# Escorna_CPU_1_01.net
KiCad netlist of a schematic drawn in EAGLE
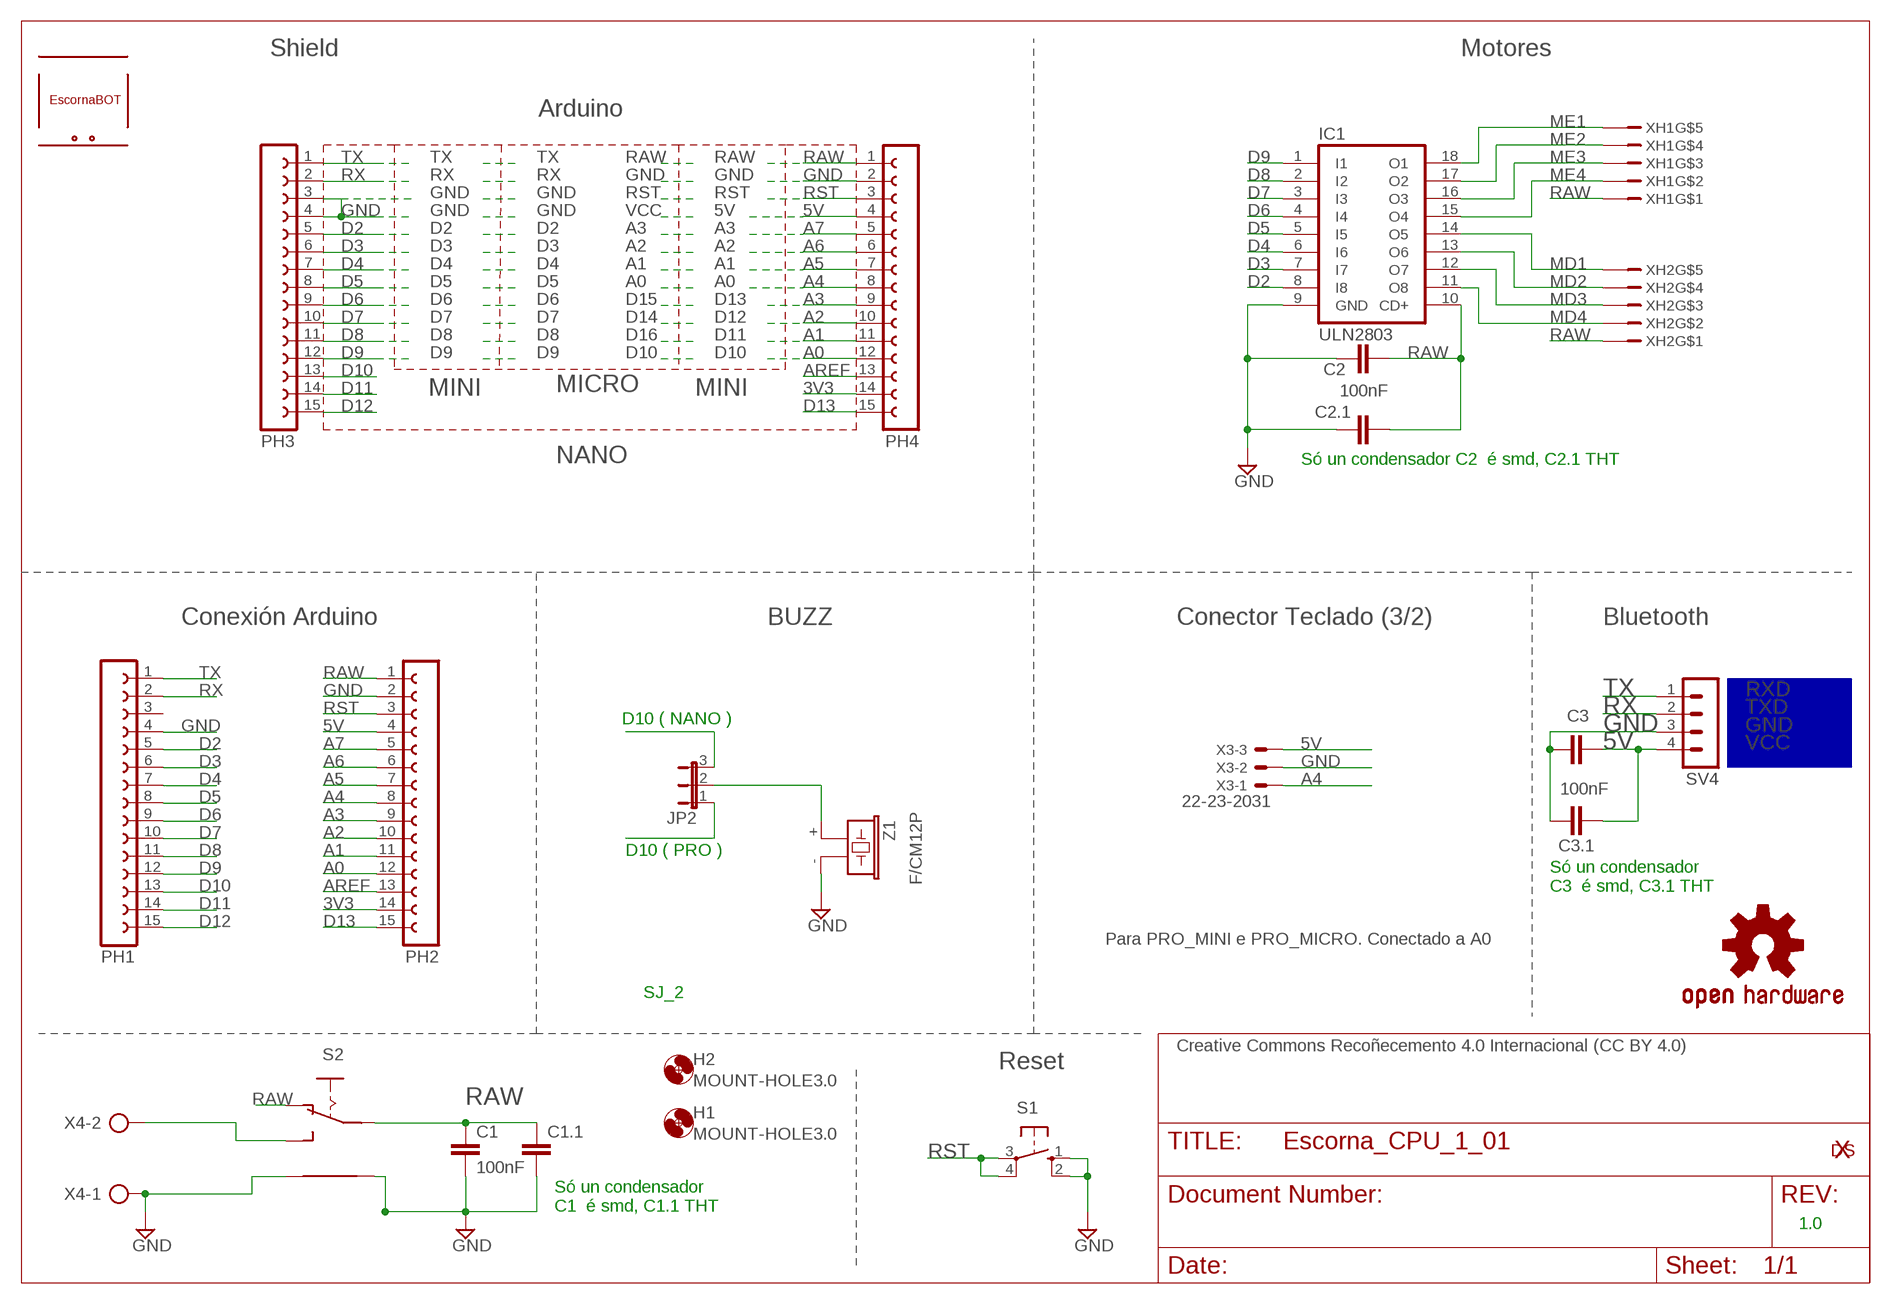
[diagram p0: schematic, sheet 1]

(export (version "E")
  (design (tool "Eeschema 10.0.6"))
  (components
    (comp (ref "C1")
      (value "100nF")
      (footprint "eagle-import:C1206")
      (libsource (lib "eagle-import") (part "C-EUC1206"))
    )
    (comp (ref "C1.1")
      (value "C-EU025-024X044")
      (footprint "eagle-import:C025-024X044")
      (libsource (lib "eagle-import") (part "C-EU025-024X044"))
    )
    (comp (ref "C2")
      (value "100nF")
      (footprint "eagle-import:C1206")
      (libsource (lib "eagle-import") (part "C-EUC1206"))
    )
    (comp (ref "C2.1")
      (value "C-EU025-024X044")
      (footprint "eagle-import:C025-024X044")
      (libsource (lib "eagle-import") (part "C-EU025-024X044"))
    )
    (comp (ref "C3")
      (value "100nF")
      (footprint "eagle-import:C1206")
      (libsource (lib "eagle-import") (part "C-EUC1206"))
    )
    (comp (ref "C3.1")
      (value "C-EU025-024X044")
      (footprint "eagle-import:C025-024X044")
      (libsource (lib "eagle-import") (part "C-EU025-024X044"))
    )
    (comp (ref "H1")
      (value "MOUNT-HOLE3.0")
      (footprint "eagle-import:3,0")
      (libsource (lib "eagle-import") (part "MOUNT-HOLE3.0"))
    )
    (comp (ref "H2")
      (value "MOUNT-HOLE3.0")
      (footprint "eagle-import:3,0")
      (libsource (lib "eagle-import") (part "MOUNT-HOLE3.0"))
    )
    (comp (ref "IC1")
      (value "ULN2803")
      (footprint "eagle-import:DIL18")
      (libsource (lib "eagle-import") (part "ULN2803A{dblquote}"))
    )
    (comp (ref "JP2")
      (value "JP2E")
      (footprint "eagle-import:JP2")
      (libsource (lib "eagle-import") (part "JP2E"))
    )
    (comp (ref "LOGO1")
      (value "OSHW-LOGOS")
      (footprint "eagle-import:OSHW-LOGO-S")
      (libsource (lib "eagle-import") (part "OSHW-LOGOS"))
    )
    (comp (ref "PH1")
      (value "FE15-1")
      (footprint "eagle-import:FE15")
      (libsource (lib "eagle-import") (part "FE15-1"))
    )
    (comp (ref "PH2")
      (value "FE15-1")
      (footprint "eagle-import:FE15")
      (libsource (lib "eagle-import") (part "FE15-1"))
    )
    (comp (ref "PH3")
      (value "FE15-1")
      (footprint "eagle-import:FE15")
      (libsource (lib "eagle-import") (part "FE15-1"))
    )
    (comp (ref "PH4")
      (value "FE15-1")
      (footprint "eagle-import:FE15")
      (libsource (lib "eagle-import") (part "FE15-1"))
    )
    (comp (ref "S1")
      (value "10-XX")
      (footprint "eagle-import:B3F-10XX")
      (fields (field (name "MPN") "B3F-1000"))
      (libsource (lib "eagle-import") (part "10-XX"))
    )
    (comp (ref "S2")
      (value "SK12F14F")
      (footprint "eagle-import:SK-12F14-G")
      (libsource (lib "eagle-import") (part "SK12F14F"))
    )
    (comp (ref "SV4")
      (value "MA04-1")
      (footprint "eagle-import:MA04-1")
      (libsource (lib "eagle-import") (part "MA04-1"))
    )
    (comp (ref "U$1")
      (value "ESCORNABOT")
      (footprint "eagle-import:ESCORNA_PEQUE")
      (libsource (lib "eagle-import") (part "ESCORNABOT"))
    )
    (comp (ref "U$6")
      (value "XDESIG")
      (footprint "eagle-import:XDESIG_CU_2")
      (libsource (lib "eagle-import") (part "XDESIG"))
    )
    (comp (ref "X3")
      (value "22-23-2031")
      (footprint "eagle-import:22-23-2031")
      (fields (field (name "MF") "MOLEX"))
      (libsource (lib "eagle-import") (part "22-23-2031"))
    )
    (comp (ref "X4")
      (value "AK500/2")
      (footprint "eagle-import:AK500_2")
      (libsource (lib "eagle-import") (part "AK500/2"))
    )
    (comp (ref "XH1")
      (value "B5B-XH-A")
      (footprint "eagle-import:B5B-XH-A")
      (libsource (lib "eagle-import") (part "B5B-XH-A"))
    )
    (comp (ref "XH2")
      (value "B5B-XH-A")
      (footprint "eagle-import:B5B-XH-A")
      (libsource (lib "eagle-import") (part "B5B-XH-A"))
    )
    (comp (ref "Z1")
      (value "F/CM12P")
      (footprint "eagle-import:F_CM12P")
      (libsource (lib "eagle-import") (part "F/CM12P"))
    )
  )
  (nets
    (net (code "1") (name "/3V3") (class "Default")
      (node (ref "PH2") (pin "14") (pinfunction "14_14") (pintype "passive"))
      (node (ref "PH4") (pin "14") (pinfunction "14_14") (pintype "passive"))
    )
    (net (code "2") (name "/5V") (class "Default")
      (node (ref "C3") (pin "2") (pinfunction "2_2") (pintype "passive"))
      (node (ref "C3.1") (pin "2") (pinfunction "2_2") (pintype "passive"))
      (node (ref "PH2") (pin "4") (pinfunction "4_4") (pintype "passive"))
      (node (ref "PH4") (pin "4") (pinfunction "4_4") (pintype "passive"))
      (node (ref "SV4") (pin "4") (pinfunction "4_4") (pintype "passive"))
      (node (ref "X3") (pin "3") (pinfunction "S_3") (pintype "passive"))
    )
    (net (code "3") (name "/A0") (class "Default")
      (node (ref "JP2") (pin "1") (pinfunction "1_1") (pintype "passive"))
      (node (ref "PH2") (pin "12") (pinfunction "12_12") (pintype "passive"))
      (node (ref "PH4") (pin "12") (pinfunction "12_12") (pintype "passive"))
    )
    (net (code "4") (name "/A1") (class "Default")
      (node (ref "PH2") (pin "11") (pinfunction "11_11") (pintype "passive"))
      (node (ref "PH4") (pin "11") (pinfunction "11_11") (pintype "passive"))
    )
    (net (code "5") (name "/A2") (class "Default")
      (node (ref "PH2") (pin "10") (pinfunction "10_10") (pintype "passive"))
      (node (ref "PH4") (pin "10") (pinfunction "10_10") (pintype "passive"))
    )
    (net (code "6") (name "/A3") (class "Default")
      (node (ref "PH2") (pin "9") (pinfunction "9_9") (pintype "passive"))
      (node (ref "PH4") (pin "9") (pinfunction "9_9") (pintype "passive"))
    )
    (net (code "7") (name "/A4") (class "Default")
      (node (ref "PH2") (pin "8") (pinfunction "8_8") (pintype "passive"))
      (node (ref "PH4") (pin "8") (pinfunction "8_8") (pintype "passive"))
      (node (ref "X3") (pin "1") (pinfunction "S_1") (pintype "passive"))
    )
    (net (code "8") (name "/A5") (class "Default")
      (node (ref "PH2") (pin "7") (pinfunction "7_7") (pintype "passive"))
      (node (ref "PH4") (pin "7") (pinfunction "7_7") (pintype "passive"))
    )
    (net (code "9") (name "/A6") (class "Default")
      (node (ref "PH2") (pin "6") (pinfunction "6_6") (pintype "passive"))
      (node (ref "PH4") (pin "6") (pinfunction "6_6") (pintype "passive"))
    )
    (net (code "10") (name "/A7") (class "Default")
      (node (ref "PH2") (pin "5") (pinfunction "5_5") (pintype "passive"))
      (node (ref "PH4") (pin "5") (pinfunction "5_5") (pintype "passive"))
    )
    (net (code "11") (name "/AREF") (class "Default")
      (node (ref "PH2") (pin "13") (pinfunction "13_13") (pintype "passive"))
      (node (ref "PH4") (pin "13") (pinfunction "13_13") (pintype "passive"))
    )
    (net (code "12") (name "/D2") (class "Default")
      (node (ref "IC1") (pin "8") (pinfunction "I8_8") (pintype "input"))
      (node (ref "PH1") (pin "5") (pinfunction "5_5") (pintype "passive"))
      (node (ref "PH3") (pin "5") (pinfunction "5_5") (pintype "passive"))
    )
    (net (code "13") (name "/D3") (class "Default")
      (node (ref "IC1") (pin "7") (pinfunction "I7_7") (pintype "input"))
      (node (ref "PH1") (pin "6") (pinfunction "6_6") (pintype "passive"))
      (node (ref "PH3") (pin "6") (pinfunction "6_6") (pintype "passive"))
    )
    (net (code "14") (name "/D4") (class "Default")
      (node (ref "IC1") (pin "6") (pinfunction "I6_6") (pintype "input"))
      (node (ref "PH1") (pin "7") (pinfunction "7_7") (pintype "passive"))
      (node (ref "PH3") (pin "7") (pinfunction "7_7") (pintype "passive"))
    )
    (net (code "15") (name "/D5") (class "Default")
      (node (ref "IC1") (pin "5") (pinfunction "I5_5") (pintype "input"))
      (node (ref "PH1") (pin "8") (pinfunction "8_8") (pintype "passive"))
      (node (ref "PH3") (pin "8") (pinfunction "8_8") (pintype "passive"))
    )
    (net (code "16") (name "/D6") (class "Default")
      (node (ref "IC1") (pin "4") (pinfunction "I4_4") (pintype "input"))
      (node (ref "PH1") (pin "9") (pinfunction "9_9") (pintype "passive"))
      (node (ref "PH3") (pin "9") (pinfunction "9_9") (pintype "passive"))
    )
    (net (code "17") (name "/D7") (class "Default")
      (node (ref "IC1") (pin "3") (pinfunction "I3_3") (pintype "input"))
      (node (ref "PH1") (pin "10") (pinfunction "10_10") (pintype "passive"))
      (node (ref "PH3") (pin "10") (pinfunction "10_10") (pintype "passive"))
    )
    (net (code "18") (name "/D8") (class "Default")
      (node (ref "IC1") (pin "2") (pinfunction "I2_2") (pintype "input"))
      (node (ref "PH1") (pin "11") (pinfunction "11_11") (pintype "passive"))
      (node (ref "PH3") (pin "11") (pinfunction "11_11") (pintype "passive"))
    )
    (net (code "19") (name "/D9") (class "Default")
      (node (ref "IC1") (pin "1") (pinfunction "I1_1") (pintype "input"))
      (node (ref "PH1") (pin "12") (pinfunction "12_12") (pintype "passive"))
      (node (ref "PH3") (pin "12") (pinfunction "12_12") (pintype "passive"))
    )
    (net (code "20") (name "/D10") (class "Default")
      (node (ref "JP2") (pin "3") (pinfunction "3_3") (pintype "passive"))
      (node (ref "PH1") (pin "13") (pinfunction "13_13") (pintype "passive"))
      (node (ref "PH3") (pin "13") (pinfunction "13_13") (pintype "passive"))
    )
    (net (code "21") (name "/D11") (class "Default")
      (node (ref "PH1") (pin "14") (pinfunction "14_14") (pintype "passive"))
      (node (ref "PH3") (pin "14") (pinfunction "14_14") (pintype "passive"))
    )
    (net (code "22") (name "/D12") (class "Default")
      (node (ref "PH1") (pin "15") (pinfunction "15_15") (pintype "passive"))
      (node (ref "PH3") (pin "15") (pinfunction "15_15") (pintype "passive"))
    )
    (net (code "23") (name "/D13") (class "Default")
      (node (ref "PH2") (pin "15") (pinfunction "15_15") (pintype "passive"))
      (node (ref "PH4") (pin "15") (pinfunction "15_15") (pintype "passive"))
    )
    (net (code "24") (name "/MD1") (class "Default")
      (node (ref "IC1") (pin "14") (pinfunction "O5_14") (pintype "open_collector"))
      (node (ref "XH2") (pin "P$5") (pinfunction "1_P$5") (pintype "passive"))
    )
    (net (code "25") (name "/MD2") (class "Default")
      (node (ref "IC1") (pin "13") (pinfunction "O6_13") (pintype "open_collector"))
      (node (ref "XH2") (pin "P$4") (pinfunction "1_P$4") (pintype "passive"))
    )
    (net (code "26") (name "/MD3") (class "Default")
      (node (ref "IC1") (pin "12") (pinfunction "O7_12") (pintype "open_collector"))
      (node (ref "XH2") (pin "P$3") (pinfunction "1_P$3") (pintype "passive"))
    )
    (net (code "27") (name "/MD4") (class "Default")
      (node (ref "IC1") (pin "11") (pinfunction "O8_11") (pintype "open_collector"))
      (node (ref "XH2") (pin "P$2") (pinfunction "1_P$2") (pintype "passive"))
    )
    (net (code "28") (name "/ME1") (class "Default")
      (node (ref "IC1") (pin "18") (pinfunction "O1_18") (pintype "open_collector"))
      (node (ref "XH1") (pin "P$5") (pinfunction "1_P$5") (pintype "passive"))
    )
    (net (code "29") (name "/ME2") (class "Default")
      (node (ref "IC1") (pin "17") (pinfunction "O2_17") (pintype "open_collector"))
      (node (ref "XH1") (pin "P$4") (pinfunction "1_P$4") (pintype "passive"))
    )
    (net (code "30") (name "/ME3") (class "Default")
      (node (ref "IC1") (pin "16") (pinfunction "O3_16") (pintype "open_collector"))
      (node (ref "XH1") (pin "P$3") (pinfunction "1_P$3") (pintype "passive"))
    )
    (net (code "31") (name "/ME4") (class "Default")
      (node (ref "IC1") (pin "15") (pinfunction "O4_15") (pintype "open_collector"))
      (node (ref "XH1") (pin "P$2") (pinfunction "1_P$2") (pintype "passive"))
    )
    (net (code "32") (name "/RAW") (class "Default")
      (node (ref "C1") (pin "1") (pinfunction "1_1") (pintype "passive"))
      (node (ref "C1.1") (pin "1") (pinfunction "1_1") (pintype "passive"))
      (node (ref "C2") (pin "2") (pinfunction "2_2") (pintype "passive"))
      (node (ref "C2.1") (pin "2") (pinfunction "2_2") (pintype "passive"))
      (node (ref "IC1") (pin "10") (pinfunction "CD+_10") (pintype "passive"))
      (node (ref "PH2") (pin "1") (pinfunction "1_1") (pintype "passive"))
      (node (ref "PH4") (pin "1") (pinfunction "1_1") (pintype "passive"))
      (node (ref "S2") (pin "P$1") (pinfunction "P_P$1") (pintype "passive"))
      (node (ref "S2") (pin "P$2") (pinfunction "O_P$2") (pintype "passive"))
      (node (ref "XH1") (pin "P$1") (pinfunction "1_P$1") (pintype "passive"))
      (node (ref "XH2") (pin "P$1") (pinfunction "1_P$1") (pintype "passive"))
    )
    (net (code "33") (name "/RST") (class "Default")
      (node (ref "PH2") (pin "3") (pinfunction "3_3") (pintype "passive"))
      (node (ref "PH4") (pin "3") (pinfunction "3_3") (pintype "passive"))
      (node (ref "S1") (pin "3") (pinfunction "P_3") (pintype "passive"))
      (node (ref "S1") (pin "4") (pinfunction "P1_4") (pintype "passive"))
    )
    (net (code "34") (name "/RX") (class "Default")
      (node (ref "PH1") (pin "2") (pinfunction "2_2") (pintype "passive"))
      (node (ref "PH3") (pin "2") (pinfunction "2_2") (pintype "passive"))
      (node (ref "SV4") (pin "2") (pinfunction "2_2") (pintype "passive"))
    )
    (net (code "35") (name "/TX") (class "Default")
      (node (ref "PH1") (pin "1") (pinfunction "1_1") (pintype "passive"))
      (node (ref "PH3") (pin "1") (pinfunction "1_1") (pintype "passive"))
      (node (ref "SV4") (pin "1") (pinfunction "1_1") (pintype "passive"))
    )
    (net (code "36") (name "GND") (class "Default")
      (node (ref "C1") (pin "2") (pinfunction "2_2") (pintype "passive"))
      (node (ref "C1.1") (pin "2") (pinfunction "2_2") (pintype "passive"))
      (node (ref "C2") (pin "1") (pinfunction "1_1") (pintype "passive"))
      (node (ref "C2.1") (pin "1") (pinfunction "1_1") (pintype "passive"))
      (node (ref "C3") (pin "1") (pinfunction "1_1") (pintype "passive"))
      (node (ref "C3.1") (pin "1") (pinfunction "1_1") (pintype "passive"))
      (node (ref "IC1") (pin "9") (pinfunction "GND_9") (pintype "power_in"))
      (node (ref "PH1") (pin "4") (pinfunction "4_4") (pintype "passive"))
      (node (ref "PH2") (pin "2") (pinfunction "2_2") (pintype "passive"))
      (node (ref "PH3") (pin "3") (pinfunction "3_3") (pintype "passive"))
      (node (ref "PH3") (pin "4") (pinfunction "4_4") (pintype "passive"))
      (node (ref "PH4") (pin "2") (pinfunction "2_2") (pintype "passive"))
      (node (ref "S1") (pin "1") (pinfunction "S_1") (pintype "passive"))
      (node (ref "S1") (pin "2") (pinfunction "S1_2") (pintype "passive"))
      (node (ref "S2") (pin "P$4") (pinfunction "P$1_P$4") (pintype "passive"))
      (node (ref "S2") (pin "P$5") (pinfunction "P$2_P$5") (pintype "bidirectional"))
      (node (ref "SV4") (pin "3") (pinfunction "3_3") (pintype "passive"))
      (node (ref "X3") (pin "2") (pinfunction "S_2") (pintype "passive"))
      (node (ref "X4") (pin "1") (pinfunction "KL_1") (pintype "passive"))
      (node (ref "Z1") (pin "-") (pinfunction "2_-") (pintype "passive"))
    )
    (net (code "37") (name "Net-(S2-S)") (class "Default")
      (node (ref "S2") (pin "P$3") (pinfunction "S_P$3") (pintype "passive"))
      (node (ref "X4") (pin "2") (pinfunction "KL_2") (pintype "passive"))
    )
    (net (code "38") (name "Net-(Z1-1)") (class "Default")
      (node (ref "JP2") (pin "2") (pinfunction "2_2") (pintype "passive"))
      (node (ref "Z1") (pin "+") (pinfunction "1_+") (pintype "passive"))
    )
    (net (code "39") (name "unconnected-(PH1-Pad3)") (class "Default")
      (node (ref "PH1") (pin "3") (pinfunction "3_3") (pintype "passive"))
    )
  )
)
